# powersupply_grid8_1.net
KiCad netlist of a schematic drawn in Altium Designer
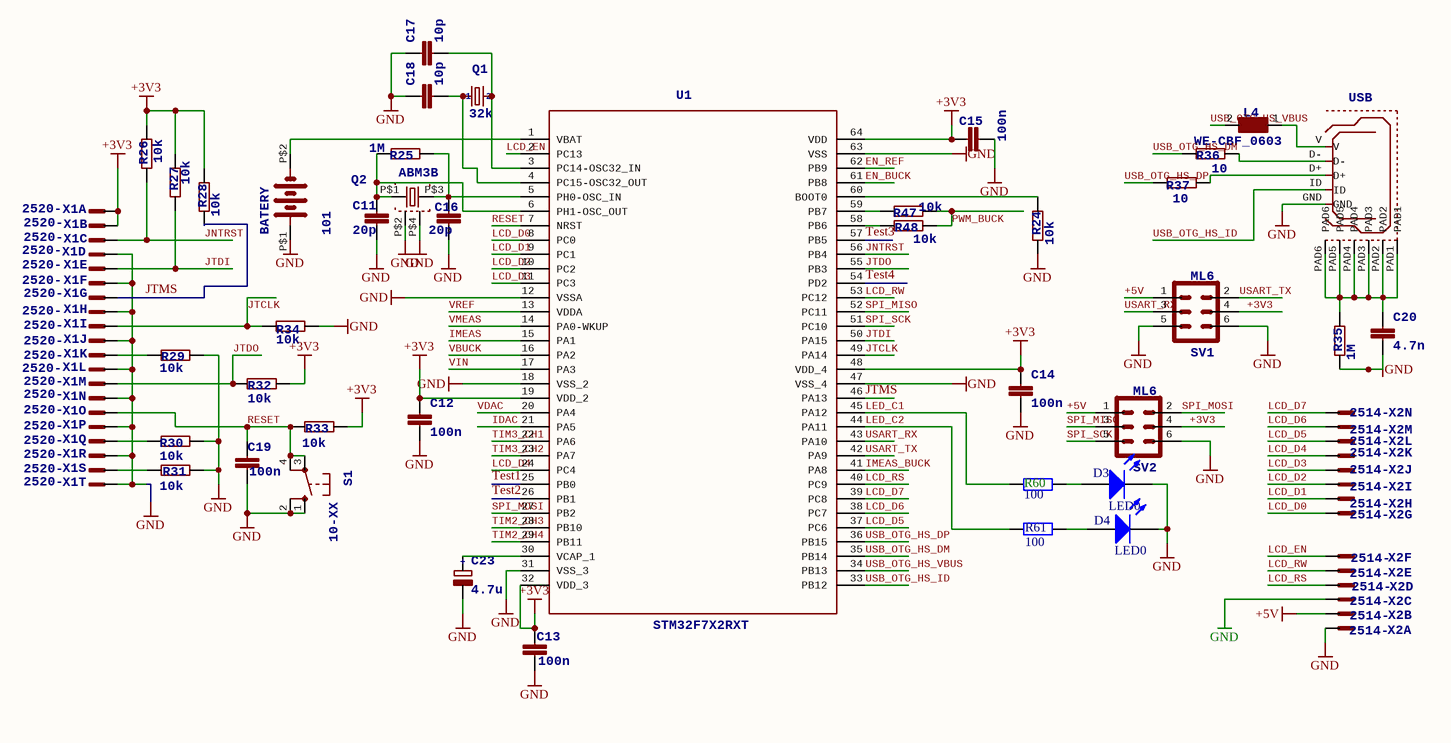
[diagram p0: powersupply_grid8_1.SchDoc]

(export (version "E")
  (design (tool "Eeschema 10.0.6"))
  (components
    (comp (ref "BATERY") (value "101") (footprint "KEYSTONE101") (libsource (lib "my_battery") (part "101")))
    (comp (ref "C11")
      (value "20p")
      (footprint "C0402")
      (description "<B>CAPACITOR</B>, European symbol")
      (libsource (lib "rcl") (part "C-EUC0402"))
    )
    (comp (ref "C12")
      (value "100n")
      (footprint "C0402")
      (description "<B>CAPACITOR</B>, European symbol")
      (libsource (lib "rcl") (part "C-EUC0402"))
    )
    (comp (ref "C13")
      (value "100n")
      (footprint "C0603")
      (description "<B>CAPACITOR</B>, European symbol")
      (libsource (lib "rcl") (part "C-EUC0603"))
    )
    (comp (ref "C14")
      (value "100n")
      (footprint "C0402")
      (description "<B>CAPACITOR</B>, European symbol")
      (libsource (lib "rcl") (part "C-EUC0402"))
    )
    (comp (ref "C15")
      (value "100n")
      (footprint "C0402")
      (description "<B>CAPACITOR</B>, European symbol")
      (libsource (lib "") (part "C-EUC0402_1"))
    )
    (comp (ref "C16")
      (value "20p")
      (footprint "C0402")
      (description "<B>CAPACITOR</B>, European symbol")
      (libsource (lib "rcl") (part "C-EUC0402"))
    )
    (comp (ref "C17")
      (value "10p")
      (footprint "C0402")
      (description "<B>CAPACITOR</B>, European symbol")
      (libsource (lib "") (part "C-EUC0402_1"))
    )
    (comp (ref "C18")
      (value "10p")
      (footprint "C0402")
      (description "<B>CAPACITOR</B>, European symbol")
      (libsource (lib "") (part "C-EUC0402_1"))
    )
    (comp (ref "C19")
      (value "100n")
      (footprint "C0402")
      (description "<B>CAPACITOR</B>, European symbol")
      (libsource (lib "rcl") (part "C-EUC0402"))
    )
    (comp (ref "C20")
      (value "4.7n")
      (footprint "C0805")
      (description "<B>CAPACITOR</B>, European symbol")
      (libsource (lib "rcl") (part "C-EUC0805"))
    )
    (comp (ref "C23")
      (value "4.7u")
      (footprint "C0805")
      (description "<B>POLARIZED CAPACITOR</B>, European symbol")
      (fields (field (name "+") "+"))
      (libsource (lib "rcl") (part "CPOL-EUE2.5-7"))
    )
    (comp (ref "D3")
      (value "LED0")
      (footprint "LED-0")
      (description "Typical INFRARED GaAs LED")
      (fields (field (name "PUBLISHER") "Altium Limited"))
      (libsource (lib "Miscellaneous Devices") (part "LED0"))
    )
    (comp (ref "D4")
      (value "LED0")
      (footprint "LED-0")
      (description "Typical INFRARED GaAs LED")
      (fields (field (name "PUBLISHER") "Altium Limited"))
      (libsource (lib "Miscellaneous Devices") (part "LED0"))
    )
    (comp (ref "L4")
      (value "WE-CBF_0603")
      (footprint "0603")
      (fields (field (name "MPN") "742792695"))
      (libsource (lib "WE-CBF") (part "WE-CBF_0603"))
    )
    (comp (ref "Q1")
      (value "32k")
      (footprint "TC26V")
      (description "<b>CRYSTAL</b>")
      (fields (field (name "1") "1") (field (name "2") "2"))
      (libsource (lib "crystal") (part "CRYSTALTC26V"))
    )
    (comp (ref "Q2") (value "ABM3B") (footprint "ABM3B") (libsource (lib "crystal_my") (part "ABM3B")))
    (comp (ref "R24")
      (value "10k")
      (footprint "R0805")
      (description "<B>RESISTOR</B>, European symbol")
      (libsource (lib "rcl") (part "R-EU_R0805"))
    )
    (comp (ref "R25")
      (value "1M")
      (footprint "R0402")
      (description "<B>RESISTOR</B>, European symbol")
      (libsource (lib "rcl") (part "R-EU_R0402"))
    )
    (comp (ref "R26")
      (value "10k")
      (footprint "R0805")
      (description "<B>RESISTOR</B>, European symbol")
      (libsource (lib "rcl") (part "R-EU_R0805"))
    )
    (comp (ref "R27")
      (value "10k")
      (footprint "R0805")
      (description "<B>RESISTOR</B>, European symbol")
      (libsource (lib "rcl") (part "R-EU_R0805"))
    )
    (comp (ref "R28")
      (value "10k")
      (footprint "R0805")
      (description "<B>RESISTOR</B>, European symbol")
      (libsource (lib "rcl") (part "R-EU_R0805"))
    )
    (comp (ref "R29")
      (value "10k")
      (footprint "R0805")
      (description "<B>RESISTOR</B>, European symbol")
      (libsource (lib "rcl") (part "R-EU_R0805"))
    )
    (comp (ref "R30")
      (value "10k")
      (footprint "R0805")
      (description "<B>RESISTOR</B>, European symbol")
      (libsource (lib "rcl") (part "R-EU_R0805"))
    )
    (comp (ref "R31")
      (value "10k")
      (footprint "R0805")
      (description "<B>RESISTOR</B>, European symbol")
      (libsource (lib "rcl") (part "R-EU_R0805"))
    )
    (comp (ref "R32")
      (value "10k")
      (footprint "R0805")
      (description "<B>RESISTOR</B>, European symbol")
      (libsource (lib "rcl") (part "R-EU_R0805"))
    )
    (comp (ref "R33")
      (value "10k")
      (footprint "R0805")
      (description "<B>RESISTOR</B>, European symbol")
      (libsource (lib "rcl") (part "R-EU_R0805"))
    )
    (comp (ref "R34")
      (value "10k")
      (footprint "R0805")
      (description "<B>RESISTOR</B>, European symbol")
      (libsource (lib "rcl") (part "R-EU_R0805"))
    )
    (comp (ref "R35")
      (value "1M")
      (footprint "R0805")
      (description "<B>RESISTOR</B>, European symbol")
      (libsource (lib "rcl") (part "R-EU_R0805"))
    )
    (comp (ref "R36")
      (value "10")
      (footprint "R0805")
      (description "<B>RESISTOR</B>, European symbol")
      (libsource (lib "rcl") (part "R-EU_R0805"))
    )
    (comp (ref "R37")
      (value "10")
      (footprint "R0805")
      (description "<B>RESISTOR</B>, European symbol")
      (libsource (lib "rcl") (part "R-EU_R0805"))
    )
    (comp (ref "R47")
      (value "10k")
      (footprint "R0805")
      (description "<B>RESISTOR</B>, European symbol")
      (libsource (lib "rcl") (part "R-EU_R0805"))
    )
    (comp (ref "R48")
      (value "10k")
      (footprint "R0805")
      (description "<B>RESISTOR</B>, European symbol")
      (libsource (lib "rcl") (part "R-EU_R0805"))
    )
    (comp (ref "R60")
      (value "100")
      (footprint "6-0805_L")
      (description "Resistor")
      (fields (field (name "Comment") "Res2") (field (name "PUBLISHER") "Altium Limited"))
      (libsource (lib "Miscellaneous Devices") (part "Res2"))
    )
    (comp (ref "R61")
      (value "100")
      (footprint "6-0805_L")
      (description "Resistor")
      (fields (field (name "Comment") "Res2") (field (name "PUBLISHER") "Altium Limited"))
      (libsource (lib "Miscellaneous Devices") (part "Res2"))
    )
    (comp (ref "S1")
      (value "10-XX")
      (footprint "B3F-10XX")
      (description "<b>OMRON SWITCH</b>")
      (fields (field (name "MPN") "B3F-1000"))
      (libsource (lib "switch-omron") (part "10-XX"))
    )
    (comp (ref "SV1")
      (value "ML6")
      (footprint "ML6")
      (description "<b>HARTING</b>")
      (libsource (lib "con-harting-ml") (part "ML6"))
    )
    (comp (ref "SV2")
      (value "ML6")
      (footprint "ML6")
      (description "<b>HARTING</b>")
      (libsource (lib "con-harting-ml") (part "ML6"))
    )
    (comp (ref "U$6")
      (value "USB_MICROB")
      (footprint "USB_MICROB_PACKAGE")
      (description "This is the hirose ZX62-B-5PA(11) MICRO-USB B Type female connection.")
      (fields (field (name "USB") "USB"))
      (libsource (lib "usb_hinrose") (part "USB_MICROB"))
    )
    (comp (ref "U1")
      (value "STM32F7X2RXT")
      (footprint "LQFP64-10X10MM")
      (fields (field (name "MANUFACTURER_PART_NUMBER") "stm32f7x2rxt"))
      (libsource (lib "STM32F732RE") (part "STM32F7X2RXT"))
    )
    (comp (ref "X1")
      (value "2520-")
      (footprint "PAK100/2500-20")
      (description "<b>3M (TM) Pak 100 4-Wall Header</b><p>\nSource: 3M")
      (libsource (lib "con-3m") (part "2520-"))
    )
    (comp (ref "X2")
      (value "2514-")
      (footprint "PAK100/2500-14")
      (description "<b>3M (TM) Pak 100 4-Wall Header</b><p>\nSource: 3M")
      (libsource (lib "con-3m") (part "2514-"))
    )
  )
  (nets
    (net (code "1") (name "+3V3") (class "Default")
      (node (ref "C12") (pin "1") (pinfunction "1_1") (pintype "passive"))
      (node (ref "C13") (pin "1") (pinfunction "1_1") (pintype "passive"))
      (node (ref "C14") (pin "1") (pinfunction "1_1") (pintype "passive"))
      (node (ref "C15") (pin "1") (pinfunction "1_1") (pintype "passive"))
      (node (ref "R26") (pin "2") (pinfunction "2_2") (pintype "passive"))
      (node (ref "R27") (pin "2") (pinfunction "2_2") (pintype "passive"))
      (node (ref "R28") (pin "2") (pinfunction "2_2") (pintype "passive"))
      (node (ref "R32") (pin "1") (pinfunction "1_1") (pintype "passive"))
      (node (ref "R33") (pin "1") (pinfunction "1_1") (pintype "passive"))
      (node (ref "SV1") (pin "4") (pinfunction "4_4") (pintype "passive"))
      (node (ref "SV2") (pin "4") (pinfunction "4_4") (pintype "passive"))
      (node (ref "U1") (pin "19") (pinfunction "VDD_2_19") (pintype "power_in"))
      (node (ref "U1") (pin "32") (pinfunction "VDD_3_32") (pintype "power_in"))
      (node (ref "U1") (pin "48") (pinfunction "VDD_4_48") (pintype "power_in"))
      (node (ref "U1") (pin "64") (pinfunction "VDD_64") (pintype "power_in"))
      (node (ref "X1") (pin "1") (pinfunction "KL_1") (pintype "passive"))
      (node (ref "X1") (pin "2") (pinfunction "KL_2") (pintype "passive"))
    )
    (net (code "2") (name "+5V") (class "Default")
      (node (ref "SV1") (pin "1") (pinfunction "1_1") (pintype "passive"))
      (node (ref "SV2") (pin "1") (pinfunction "1_1") (pintype "passive"))
      (node (ref "X2") (pin "2") (pinfunction "KL_2") (pintype "passive"))
    )
    (net (code "3") (name "/EN_BUCK") (class "Default")
      (node (ref "U1") (pin "61") (pinfunction "PB8_61") (pintype "passive"))
    )
    (net (code "4") (name "/EN_REF") (class "Default")
      (node (ref "U1") (pin "62") (pinfunction "PB9_62") (pintype "passive"))
    )
    (net (code "5") (name "/IDAC") (class "Default")
      (node (ref "U1") (pin "21") (pinfunction "PA5_21") (pintype "passive"))
    )
    (net (code "6") (name "/IMEAS") (class "Default")
      (node (ref "U1") (pin "15") (pinfunction "PA1_15") (pintype "passive"))
    )
    (net (code "7") (name "/IMEAS_BUCK") (class "Default")
      (node (ref "U1") (pin "41") (pinfunction "PA8_41") (pintype "passive"))
    )
    (net (code "8") (name "/JNTRST") (class "Default")
      (node (ref "R26") (pin "1") (pinfunction "1_1") (pintype "passive"))
      (node (ref "U1") (pin "56") (pinfunction "PB4_56") (pintype "passive"))
      (node (ref "X1") (pin "3") (pinfunction "KL_3") (pintype "passive"))
    )
    (net (code "9") (name "/JTCLK") (class "Default")
      (node (ref "R34") (pin "2") (pinfunction "2_2") (pintype "passive"))
      (node (ref "U1") (pin "49") (pinfunction "PA14_49") (pintype "passive"))
      (node (ref "X1") (pin "9") (pinfunction "KL_9") (pintype "passive"))
    )
    (net (code "10") (name "/JTDI") (class "Default")
      (node (ref "R27") (pin "1") (pinfunction "1_1") (pintype "passive"))
      (node (ref "U1") (pin "50") (pinfunction "PA15_50") (pintype "passive"))
      (node (ref "X1") (pin "5") (pinfunction "KL_5") (pintype "passive"))
    )
    (net (code "11") (name "/JTDO") (class "Default")
      (node (ref "R32") (pin "2") (pinfunction "2_2") (pintype "passive"))
      (node (ref "U1") (pin "55") (pinfunction "PB3_55") (pintype "passive"))
      (node (ref "X1") (pin "13") (pinfunction "KL_13") (pintype "passive"))
    )
    (net (code "12") (name "/JTMS") (class "Default")
      (node (ref "R28") (pin "1") (pinfunction "1_1") (pintype "passive"))
      (node (ref "U1") (pin "46") (pinfunction "PA13_46") (pintype "passive"))
      (node (ref "X1") (pin "7") (pinfunction "KL_7") (pintype "passive"))
    )
    (net (code "13") (name "/LCD_D0") (class "Default")
      (node (ref "U1") (pin "8") (pinfunction "PC0_8") (pintype "passive"))
      (node (ref "X2") (pin "7") (pinfunction "KL_7") (pintype "passive"))
    )
    (net (code "14") (name "/LCD_D1") (class "Default")
      (node (ref "U1") (pin "9") (pinfunction "PC1_9") (pintype "passive"))
      (node (ref "X2") (pin "8") (pinfunction "KL_8") (pintype "passive"))
    )
    (net (code "15") (name "/LCD_D2") (class "Default")
      (node (ref "U1") (pin "10") (pinfunction "PC2_10") (pintype "passive"))
      (node (ref "X2") (pin "9") (pinfunction "KL_9") (pintype "passive"))
    )
    (net (code "16") (name "/LCD_D3") (class "Default")
      (node (ref "U1") (pin "11") (pinfunction "PC3_11") (pintype "passive"))
      (node (ref "X2") (pin "10") (pinfunction "KL_10") (pintype "passive"))
    )
    (net (code "17") (name "/LCD_D4") (class "Default")
      (node (ref "U1") (pin "24") (pinfunction "PC4_24") (pintype "passive"))
      (node (ref "X2") (pin "11") (pinfunction "KL_11") (pintype "passive"))
    )
    (net (code "18") (name "/LCD_D5") (class "Default")
      (node (ref "U1") (pin "37") (pinfunction "PC6_37") (pintype "passive"))
      (node (ref "X2") (pin "12") (pinfunction "KL_12") (pintype "passive"))
    )
    (net (code "19") (name "/LCD_D6") (class "Default")
      (node (ref "U1") (pin "38") (pinfunction "PC7_38") (pintype "passive"))
      (node (ref "X2") (pin "13") (pinfunction "KL_13") (pintype "passive"))
    )
    (net (code "20") (name "/LCD_D7") (class "Default")
      (node (ref "U1") (pin "39") (pinfunction "PC8_39") (pintype "passive"))
      (node (ref "X2") (pin "14") (pinfunction "KL_14") (pintype "passive"))
    )
    (net (code "21") (name "/LCD_EN") (class "Default")
      (node (ref "U1") (pin "2") (pinfunction "PC13_2") (pintype "passive"))
      (node (ref "X2") (pin "6") (pinfunction "KL_6") (pintype "passive"))
    )
    (net (code "22") (name "/LCD_RS") (class "Default")
      (node (ref "U1") (pin "40") (pinfunction "PC9_40") (pintype "passive"))
      (node (ref "X2") (pin "4") (pinfunction "KL_4") (pintype "passive"))
    )
    (net (code "23") (name "/LCD_RW") (class "Default")
      (node (ref "U1") (pin "53") (pinfunction "PC12_53") (pintype "passive"))
      (node (ref "X2") (pin "5") (pinfunction "KL_5") (pintype "passive"))
    )
    (net (code "24") (name "/LED_C1") (class "Default")
      (node (ref "R60") (pin "1") (pinfunction "1_1") (pintype "passive"))
      (node (ref "U1") (pin "45") (pinfunction "PA12_45") (pintype "passive"))
    )
    (net (code "25") (name "/LED_C2") (class "Default")
      (node (ref "R61") (pin "1") (pinfunction "1_1") (pintype "passive"))
      (node (ref "U1") (pin "44") (pinfunction "PA11_44") (pintype "passive"))
    )
    (net (code "26") (name "/PWM_BUCK") (class "Default")
      (node (ref "R47") (pin "1") (pinfunction "1_1") (pintype "passive"))
      (node (ref "R48") (pin "1") (pinfunction "1_1") (pintype "passive"))
    )
    (net (code "27") (name "/RESET") (class "Default")
      (node (ref "C19") (pin "1") (pinfunction "1_1") (pintype "passive"))
      (node (ref "R33") (pin "2") (pinfunction "2_2") (pintype "passive"))
      (node (ref "S1") (pin "3") (pinfunction "P_3") (pintype "passive"))
      (node (ref "S1") (pin "4") (pinfunction "P1_4") (pintype "passive"))
      (node (ref "U1") (pin "7") (pinfunction "NRST_7") (pintype "passive"))
      (node (ref "X1") (pin "15") (pinfunction "KL_15") (pintype "passive"))
    )
    (net (code "28") (name "/SPI_MISO") (class "Default")
      (node (ref "SV2") (pin "3") (pinfunction "3_3") (pintype "passive"))
      (node (ref "U1") (pin "52") (pinfunction "PC11_52") (pintype "passive"))
    )
    (net (code "29") (name "/SPI_MOSI") (class "Default")
      (node (ref "SV2") (pin "2") (pinfunction "2_2") (pintype "passive"))
      (node (ref "U1") (pin "27") (pinfunction "PB2_27") (pintype "passive"))
    )
    (net (code "30") (name "/SPI_SCK") (class "Default")
      (node (ref "SV2") (pin "5") (pinfunction "5_5") (pintype "passive"))
      (node (ref "U1") (pin "51") (pinfunction "PC10_51") (pintype "passive"))
    )
    (net (code "31") (name "/TIM2_CH3") (class "Default")
      (node (ref "U1") (pin "28") (pinfunction "PB10_28") (pintype "passive"))
    )
    (net (code "32") (name "/TIM2_CH4") (class "Default")
      (node (ref "U1") (pin "29") (pinfunction "PB11_29") (pintype "passive"))
    )
    (net (code "33") (name "/TIM3_CH1") (class "Default")
      (node (ref "U1") (pin "22") (pinfunction "PA6_22") (pintype "passive"))
    )
    (net (code "34") (name "/TIM3_CH2") (class "Default")
      (node (ref "U1") (pin "23") (pinfunction "PA7_23") (pintype "passive"))
    )
    (net (code "35") (name "/Test1") (class "Default")
      (node (ref "U1") (pin "25") (pinfunction "PB0_25") (pintype "passive"))
    )
    (net (code "36") (name "/Test2") (class "Default")
      (node (ref "U1") (pin "26") (pinfunction "PB1_26") (pintype "passive"))
    )
    (net (code "37") (name "/Test3") (class "Default")
      (node (ref "U1") (pin "57") (pinfunction "PB5_57") (pintype "passive"))
    )
    (net (code "38") (name "/Test4") (class "Default")
      (node (ref "U1") (pin "54") (pinfunction "PD2_54") (pintype "passive"))
    )
    (net (code "39") (name "/USART_RX") (class "Default")
      (node (ref "SV1") (pin "3") (pinfunction "3_3") (pintype "passive"))
      (node (ref "U1") (pin "43") (pinfunction "PA10_43") (pintype "passive"))
    )
    (net (code "40") (name "/USART_TX") (class "Default")
      (node (ref "SV1") (pin "2") (pinfunction "2_2") (pintype "passive"))
      (node (ref "U1") (pin "42") (pinfunction "PA9_42") (pintype "passive"))
    )
    (net (code "41") (name "/USB_OTG_HS_DM") (class "Default")
      (node (ref "R36") (pin "2") (pinfunction "2_2") (pintype "passive"))
      (node (ref "U1") (pin "35") (pinfunction "PB14_35") (pintype "passive"))
    )
    (net (code "42") (name "/USB_OTG_HS_DP") (class "Default")
      (node (ref "R37") (pin "2") (pinfunction "2_2") (pintype "passive"))
      (node (ref "U1") (pin "36") (pinfunction "PB15_36") (pintype "passive"))
    )
    (net (code "43") (name "/USB_OTG_HS_ID") (class "Default")
      (node (ref "U$6") (pin "ID") (pinfunction "ID_ID") (pintype "passive"))
      (node (ref "U1") (pin "33") (pinfunction "PB12_33") (pintype "passive"))
    )
    (net (code "44") (name "/USB_OTG_HS_VBUS") (class "Default")
      (node (ref "L4") (pin "2") (pinfunction "2_2") (pintype "passive"))
      (node (ref "U1") (pin "34") (pinfunction "PB13_34") (pintype "passive"))
    )
    (net (code "45") (name "/VBUCK") (class "Default")
      (node (ref "U1") (pin "16") (pinfunction "PA2_16") (pintype "passive"))
    )
    (net (code "46") (name "/VDAC") (class "Default")
      (node (ref "U1") (pin "20") (pinfunction "PA4_20") (pintype "passive"))
    )
    (net (code "47") (name "/VIN") (class "Default")
      (node (ref "U1") (pin "17") (pinfunction "PA3_17") (pintype "passive"))
    )
    (net (code "48") (name "/VMEAS") (class "Default")
      (node (ref "U1") (pin "14") (pinfunction "PA0-WKUP_14") (pintype "passive"))
    )
    (net (code "49") (name "/VREF") (class "Default")
      (node (ref "U1") (pin "13") (pinfunction "VDDA_13") (pintype "power_in"))
    )
    (net (code "50") (name "GND") (class "Default")
      (node (ref "BATERY") (pin "P$1") (pinfunction "+_P$1") (pintype "passive"))
      (node (ref "C11") (pin "2") (pinfunction "2_2") (pintype "passive"))
      (node (ref "C12") (pin "2") (pinfunction "2_2") (pintype "passive"))
      (node (ref "C13") (pin "2") (pinfunction "2_2") (pintype "passive"))
      (node (ref "C14") (pin "2") (pinfunction "2_2") (pintype "passive"))
      (node (ref "C15") (pin "2") (pinfunction "2_2") (pintype "passive"))
      (node (ref "C16") (pin "2") (pinfunction "2_2") (pintype "passive"))
      (node (ref "C17") (pin "1") (pinfunction "1_1") (pintype "passive"))
      (node (ref "C18") (pin "1") (pinfunction "1_1") (pintype "passive"))
      (node (ref "C19") (pin "2") (pinfunction "2_2") (pintype "passive"))
      (node (ref "C20") (pin "2") (pinfunction "2_2") (pintype "passive"))
      (node (ref "C23") (pin "-") (pinfunction "-_-") (pintype "passive"))
      (node (ref "D3") (pin "2") (pinfunction "K_2") (pintype "passive"))
      (node (ref "D4") (pin "2") (pinfunction "K_2") (pintype "passive"))
      (node (ref "Q2") (pin "P$2") (pinfunction "2_P$2") (pintype "passive"))
      (node (ref "Q2") (pin "P$4") (pinfunction "4_P$4") (pintype "passive"))
      (node (ref "R24") (pin "1") (pinfunction "1_1") (pintype "passive"))
      (node (ref "R29") (pin "1") (pinfunction "1_1") (pintype "passive"))
      (node (ref "R30") (pin "1") (pinfunction "1_1") (pintype "passive"))
      (node (ref "R31") (pin "1") (pinfunction "1_1") (pintype "passive"))
      (node (ref "R34") (pin "1") (pinfunction "1_1") (pintype "passive"))
      (node (ref "R35") (pin "1") (pinfunction "1_1") (pintype "passive"))
      (node (ref "S1") (pin "1") (pinfunction "S_1") (pintype "passive"))
      (node (ref "S1") (pin "2") (pinfunction "S1_2") (pintype "passive"))
      (node (ref "SV1") (pin "5") (pinfunction "5_5") (pintype "passive"))
      (node (ref "SV1") (pin "6") (pinfunction "6_6") (pintype "passive"))
      (node (ref "SV2") (pin "6") (pinfunction "6_6") (pintype "passive"))
      (node (ref "U$6") (pin "GND") (pinfunction "GND_GND") (pintype "passive"))
      (node (ref "U1") (pin "12") (pinfunction "VSSA_12") (pintype "power_in"))
      (node (ref "U1") (pin "18") (pinfunction "VSS_2_18") (pintype "power_in"))
      (node (ref "U1") (pin "31") (pinfunction "VSS_3_31") (pintype "power_in"))
      (node (ref "U1") (pin "47") (pinfunction "VSS_4_47") (pintype "power_in"))
      (node (ref "U1") (pin "63") (pinfunction "VSS_63") (pintype "power_in"))
      (node (ref "X1") (pin "10") (pinfunction "KL_10") (pintype "passive"))
      (node (ref "X1") (pin "12") (pinfunction "KL_12") (pintype "passive"))
      (node (ref "X1") (pin "14") (pinfunction "KL_14") (pintype "passive"))
      (node (ref "X1") (pin "16") (pinfunction "KL_16") (pintype "passive"))
      (node (ref "X1") (pin "18") (pinfunction "KL_18") (pintype "passive"))
      (node (ref "X1") (pin "20") (pinfunction "KL_20") (pintype "passive"))
      (node (ref "X1") (pin "4") (pinfunction "KL_4") (pintype "passive"))
      (node (ref "X1") (pin "6") (pinfunction "KL_6") (pintype "passive"))
      (node (ref "X1") (pin "8") (pinfunction "KL_8") (pintype "passive"))
      (node (ref "X2") (pin "1") (pinfunction "KL_1") (pintype "passive"))
      (node (ref "X2") (pin "3") (pinfunction "KL_3") (pintype "passive"))
    )
    (net (code "51") (name "Net-(BATERY--)") (class "Default")
      (node (ref "BATERY") (pin "P$2") (pinfunction "-_P$2") (pintype "passive"))
      (node (ref "U1") (pin "1") (pinfunction "VBAT_1") (pintype "power_in"))
    )
    (net (code "52") (name "Net-(C20-Pad1)") (class "Default")
      (node (ref "C20") (pin "1") (pinfunction "1_1") (pintype "passive"))
      (node (ref "R35") (pin "2") (pinfunction "2_2") (pintype "passive"))
      (node (ref "U$6") (pin "PAD1") (pinfunction "PAD1_PAD1") (pintype "passive"))
      (node (ref "U$6") (pin "PAD2") (pinfunction "PAD2_PAD2") (pintype "passive"))
      (node (ref "U$6") (pin "PAD3") (pinfunction "PAD3_PAD3") (pintype "passive"))
      (node (ref "U$6") (pin "PAD4") (pinfunction "PAD4_PAD4") (pintype "passive"))
      (node (ref "U$6") (pin "PAD5") (pinfunction "PAD5_PAD5") (pintype "passive"))
      (node (ref "U$6") (pin "PAD6") (pinfunction "PAD6_PAD6") (pintype "passive"))
    )
    (net (code "53") (name "Net-(D3-A)") (class "Default")
      (node (ref "D3") (pin "1") (pinfunction "A_1") (pintype "passive"))
      (node (ref "R60") (pin "2") (pinfunction "2_2") (pintype "passive"))
    )
    (net (code "54") (name "Net-(D4-A)") (class "Default")
      (node (ref "D4") (pin "1") (pinfunction "A_1") (pintype "passive"))
      (node (ref "R61") (pin "2") (pinfunction "2_2") (pintype "passive"))
    )
    (net (code "55") (name "Net-(L4-Pad1)") (class "Default")
      (node (ref "L4") (pin "1") (pinfunction "1_1") (pintype "passive"))
      (node (ref "U$6") (pin "V") (pinfunction "V_V") (pintype "passive"))
    )
    (net (code "56") (name "Net-(Q2-1)") (class "Default")
      (node (ref "C11") (pin "1") (pinfunction "1_1") (pintype "passive"))
      (node (ref "Q2") (pin "P$1") (pinfunction "1_P$1") (pintype "passive"))
      (node (ref "R25") (pin "2") (pinfunction "2_2") (pintype "passive"))
      (node (ref "U1") (pin "6") (pinfunction "PH1-OSC_OUT_6") (pintype "passive"))
    )
    (net (code "57") (name "Net-(Q2-3)") (class "Default")
      (node (ref "C16") (pin "1") (pinfunction "1_1") (pintype "passive"))
      (node (ref "Q2") (pin "P$3") (pinfunction "3_P$3") (pintype "passive"))
      (node (ref "R25") (pin "1") (pinfunction "1_1") (pintype "passive"))
      (node (ref "U1") (pin "5") (pinfunction "PH0-OSC_IN_5") (pintype "passive"))
    )
    (net (code "58") (name "Net-(R36-Pad1)") (class "Default")
      (node (ref "R36") (pin "1") (pinfunction "1_1") (pintype "passive"))
      (node (ref "U$6") (pin "D-") (pinfunction "D-_D-") (pintype "passive"))
    )
    (net (code "59") (name "Net-(R37-Pad1)") (class "Default")
      (node (ref "R37") (pin "1") (pinfunction "1_1") (pintype "passive"))
      (node (ref "U$6") (pin "D+") (pinfunction "D+_D+") (pintype "passive"))
    )
    (net (code "60") (name "Net-(U1-BOOT0)") (class "Default")
      (node (ref "R24") (pin "2") (pinfunction "2_2") (pintype "passive"))
      (node (ref "U1") (pin "60") (pinfunction "BOOT0_60") (pintype "passive"))
    )
    (net (code "61") (name "Net-(U1-PB6)") (class "Default")
      (node (ref "R48") (pin "2") (pinfunction "2_2") (pintype "passive"))
      (node (ref "U1") (pin "58") (pinfunction "PB6_58") (pintype "passive"))
    )
    (net (code "62") (name "Net-(U1-PB7)") (class "Default")
      (node (ref "R47") (pin "2") (pinfunction "2_2") (pintype "passive"))
      (node (ref "U1") (pin "59") (pinfunction "PB7_59") (pintype "passive"))
    )
    (net (code "63") (name "Net-(U1-PC14-OSC32_IN)") (class "Default")
      (node (ref "C17") (pin "2") (pinfunction "2_2") (pintype "passive"))
      (node (ref "Q1") (pin "2") (pinfunction "2_2") (pintype "passive"))
      (node (ref "U1") (pin "3") (pinfunction "PC14-OSC32_IN_3") (pintype "passive"))
    )
    (net (code "64") (name "Net-(U1-PC15-OSC32_OUT)") (class "Default")
      (node (ref "C18") (pin "2") (pinfunction "2_2") (pintype "passive"))
      (node (ref "Q1") (pin "1") (pinfunction "1_1") (pintype "passive"))
      (node (ref "U1") (pin "4") (pinfunction "PC15-OSC32_OUT_4") (pintype "passive"))
    )
    (net (code "65") (name "Net-(U1-VCAP_1)") (class "Default")
      (node (ref "C23") (pin "+") (pinfunction "+_+") (pintype "passive"))
      (node (ref "U1") (pin "30") (pinfunction "VCAP_1_30") (pintype "power_in"))
    )
    (net (code "66") (name "Net-(X1K-KL)") (class "Default")
      (node (ref "R29") (pin "2") (pinfunction "2_2") (pintype "passive"))
      (node (ref "X1") (pin "11") (pinfunction "KL_11") (pintype "passive"))
    )
    (net (code "67") (name "Net-(X1Q-KL)") (class "Default")
      (node (ref "R30") (pin "2") (pinfunction "2_2") (pintype "passive"))
      (node (ref "X1") (pin "17") (pinfunction "KL_17") (pintype "passive"))
    )
    (net (code "68") (name "Net-(X1S-KL)") (class "Default")
      (node (ref "R31") (pin "2") (pinfunction "2_2") (pintype "passive"))
      (node (ref "X1") (pin "19") (pinfunction "KL_19") (pintype "passive"))
    )
  )
)
